# STM32.net
KiCad netlist of a schematic drawn in Altium Designer
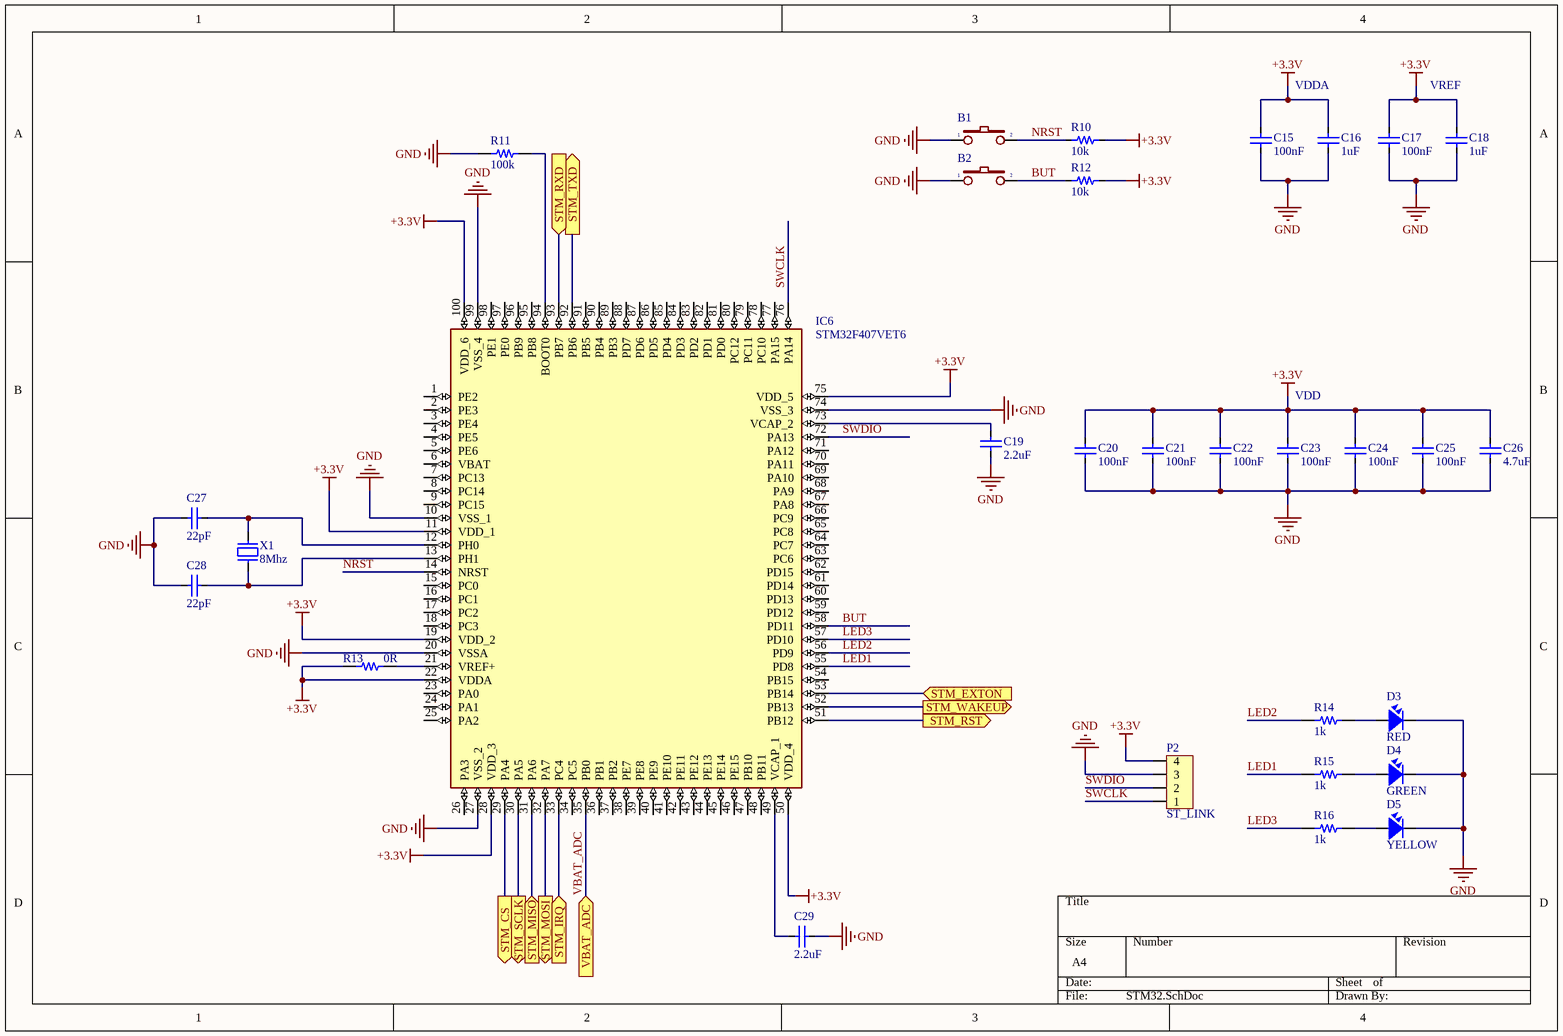
[diagram p0: STM32.SchDoc]

(export (version "E")
  (design (tool "Eeschema 10.0.6"))
  (components
    (comp (ref "B1")
      (value "Button 3x4x2.5")
      (footprint "Button 3x4x2.5")
      (libsource (lib "Dung Library") (part "Button 3x4x2.5"))
    )
    (comp (ref "B2")
      (value "Button 3x4x2.5")
      (footprint "BUTTON NGHIENG")
      (libsource (lib "Dung Library") (part "Button 3x4x2.5"))
    )
    (comp (ref "C15")
      (value "100nF")
      (footprint "CAP_0603")
      (description "Capacitor")
      (fields (field (name "PUBLISHER") "Altium Limited"))
      (libsource (lib "My Library") (part "CapSMD"))
    )
    (comp (ref "C16")
      (value "1uF")
      (footprint "CAP_0603")
      (description "Capacitor")
      (fields (field (name "PUBLISHER") "Altium Limited"))
      (libsource (lib "My Library") (part "CapSMD"))
    )
    (comp (ref "C17")
      (value "100nF")
      (footprint "CAP_0603")
      (description "Capacitor")
      (fields (field (name "PUBLISHER") "Altium Limited"))
      (libsource (lib "My Library") (part "CapSMD"))
    )
    (comp (ref "C18")
      (value "1uF")
      (footprint "CAP_0603")
      (description "Capacitor")
      (fields (field (name "PUBLISHER") "Altium Limited"))
      (libsource (lib "My Library") (part "CapSMD"))
    )
    (comp (ref "C19")
      (value "2.2uF")
      (footprint "CAP_0603")
      (description "Capacitor")
      (fields (field (name "PUBLISHER") "Altium Limited"))
      (libsource (lib "My Library") (part "CapSMD"))
    )
    (comp (ref "C20")
      (value "100nF")
      (footprint "CAP_0603")
      (description "Capacitor")
      (fields (field (name "PUBLISHER") "Altium Limited"))
      (libsource (lib "My Library") (part "CapSMD"))
    )
    (comp (ref "C21")
      (value "100nF")
      (footprint "CAP_0603")
      (description "Capacitor")
      (fields (field (name "PUBLISHER") "Altium Limited"))
      (libsource (lib "My Library") (part "CapSMD"))
    )
    (comp (ref "C22")
      (value "100nF")
      (footprint "CAP_0603")
      (description "Capacitor")
      (fields (field (name "PUBLISHER") "Altium Limited"))
      (libsource (lib "My Library") (part "CapSMD"))
    )
    (comp (ref "C23")
      (value "100nF")
      (footprint "CAP_0603")
      (description "Capacitor")
      (fields (field (name "PUBLISHER") "Altium Limited"))
      (libsource (lib "My Library") (part "CapSMD"))
    )
    (comp (ref "C24")
      (value "100nF")
      (footprint "CAP_0603")
      (description "Capacitor")
      (fields (field (name "PUBLISHER") "Altium Limited"))
      (libsource (lib "My Library") (part "CapSMD"))
    )
    (comp (ref "C25")
      (value "100nF")
      (footprint "CAP_0603")
      (description "Capacitor")
      (fields (field (name "PUBLISHER") "Altium Limited"))
      (libsource (lib "My Library") (part "CapSMD"))
    )
    (comp (ref "C26")
      (value "4.7uF")
      (footprint "CAP_0603")
      (description "Capacitor")
      (fields (field (name "PUBLISHER") "Altium Limited"))
      (libsource (lib "My Library") (part "CapSMD"))
    )
    (comp (ref "C27")
      (value "22pF")
      (footprint "CAP_0603")
      (description "Capacitor")
      (fields (field (name "PUBLISHER") "Altium Limited"))
      (libsource (lib "My Library") (part "CapSMD"))
    )
    (comp (ref "C28")
      (value "22pF")
      (footprint "CAP_0603")
      (description "Capacitor")
      (fields (field (name "PUBLISHER") "Altium Limited"))
      (libsource (lib "My Library") (part "CapSMD"))
    )
    (comp (ref "C29")
      (value "2.2uF")
      (footprint "CAP_0603")
      (description "Capacitor")
      (fields (field (name "PUBLISHER") "Altium Limited"))
      (libsource (lib "My Library") (part "CapSMD"))
    )
    (comp (ref "D3")
      (value "RED")
      (footprint "LED-0603-Red")
      (description "LED Single colour Green and Red")
      (libsource (lib "My Library") (part "LED"))
    )
    (comp (ref "D4")
      (value "GREEN")
      (footprint "LED-0603-Green")
      (description "LED Single colour Green and Red")
      (libsource (lib "My Library") (part "LED"))
    )
    (comp (ref "D5")
      (value "YELLOW")
      (footprint "LED-0603-Red")
      (description "LED Single colour Green and Red")
      (libsource (lib "My Library") (part "LED"))
    )
    (comp (ref "IC6")
      (value "STM32F407VET6")
      (footprint "STM32F407VET6")
      (libsource (lib "Dung Library") (part "STM32F407VET6"))
    )
    (comp (ref "P2")
      (value "ST_LINK")
      (footprint "HEADER4P-1.25")
      (description "Header IDC, 4 x 1 Pin Vertical 2.54mm Pitch (Non-Boxed, Male)")
      (fields
        (field (name "MANUFACTURER") "Würth Elektronik eiSos GmbH")
        (field (name "PARTNO") "613002143121")
        (field (name "CREATED BY") "Karrer Zheng")
      )
      (libsource (lib "My Library") (part "Header4"))
    )
    (comp (ref "R10")
      (value "10k")
      (footprint "RES-SMD-0603")
      (description "Resistor")
      (fields
        (field (name "MANUFACTURER") "Generic Components")
        (field (name "PUBLISHER") "Altium Hobart Technology Centre")
      )
      (libsource (lib "") (part "Resistor - SMD_1"))
    )
    (comp (ref "R11")
      (value "100k")
      (footprint "RES-SMD-0603")
      (description "Resistor")
      (fields
        (field (name "MANUFACTURER") "Generic Components")
        (field (name "PUBLISHER") "Altium Hobart Technology Centre")
      )
      (libsource (lib "My Library") (part "Resistor - SMD"))
    )
    (comp (ref "R12")
      (value "10k")
      (footprint "RES-SMD-0603")
      (description "Resistor")
      (fields
        (field (name "MANUFACTURER") "Generic Components")
        (field (name "PUBLISHER") "Altium Hobart Technology Centre")
      )
      (libsource (lib "") (part "Resistor - SMD_1"))
    )
    (comp (ref "R13")
      (value "0R")
      (footprint "RES-SMD-0603")
      (description "Resistor")
      (fields
        (field (name "MANUFACTURER") "Generic Components")
        (field (name "PUBLISHER") "Altium Hobart Technology Centre")
      )
      (libsource (lib "My Library") (part "Resistor - SMD"))
    )
    (comp (ref "R14")
      (value "1k")
      (footprint "RES-SMD-0603")
      (description "Resistor")
      (fields
        (field (name "MANUFACTURER") "Generic Components")
        (field (name "PUBLISHER") "Altium Hobart Technology Centre")
      )
      (libsource (lib "My Library") (part "Resistor - SMD"))
    )
    (comp (ref "R15")
      (value "1k")
      (footprint "RES-SMD-0603")
      (description "Resistor")
      (fields
        (field (name "MANUFACTURER") "Generic Components")
        (field (name "PUBLISHER") "Altium Hobart Technology Centre")
      )
      (libsource (lib "My Library") (part "Resistor - SMD"))
    )
    (comp (ref "R16")
      (value "1k")
      (footprint "RES-SMD-0603")
      (description "Resistor")
      (fields
        (field (name "MANUFACTURER") "Generic Components")
        (field (name "PUBLISHER") "Altium Hobart Technology Centre")
      )
      (libsource (lib "My Library") (part "Resistor - SMD"))
    )
    (comp (ref "X1")
      (value "8Mhz")
      (footprint "XTAL 5032 SMD")
      (description "Crystal For all Crystal 2pin.")
      (libsource (lib "My Library") (part "XT2"))
    )
  )
  (nets
    (net (code "1") (name "+3.3V") (class "Default")
      (node (ref "C15") (pin "2") (pinfunction "2_2") (pintype "passive"))
      (node (ref "C16") (pin "2") (pinfunction "2_2") (pintype "passive"))
      (node (ref "C17") (pin "2") (pinfunction "2_2") (pintype "passive"))
      (node (ref "C18") (pin "2") (pinfunction "2_2") (pintype "passive"))
      (node (ref "C20") (pin "2") (pinfunction "2_2") (pintype "passive"))
      (node (ref "C21") (pin "2") (pinfunction "2_2") (pintype "passive"))
      (node (ref "C22") (pin "2") (pinfunction "2_2") (pintype "passive"))
      (node (ref "C23") (pin "2") (pinfunction "2_2") (pintype "passive"))
      (node (ref "C24") (pin "2") (pinfunction "2_2") (pintype "passive"))
      (node (ref "C25") (pin "2") (pinfunction "2_2") (pintype "passive"))
      (node (ref "C26") (pin "2") (pinfunction "2_2") (pintype "passive"))
      (node (ref "IC6") (pin "100") (pinfunction "VDD_6_100") (pintype "bidirectional"))
      (node (ref "IC6") (pin "11") (pinfunction "VDD_1_11") (pintype "bidirectional"))
      (node (ref "IC6") (pin "19") (pinfunction "VDD_2_19") (pintype "bidirectional"))
      (node (ref "IC6") (pin "22") (pinfunction "VDDA_22") (pintype "bidirectional"))
      (node (ref "IC6") (pin "28") (pinfunction "VDD_3_28") (pintype "bidirectional"))
      (node (ref "IC6") (pin "50") (pinfunction "VDD_4_50") (pintype "bidirectional"))
      (node (ref "IC6") (pin "75") (pinfunction "VDD_5_75") (pintype "bidirectional"))
      (node (ref "P2") (pin "4") (pinfunction "4_4") (pintype "passive"))
      (node (ref "R10") (pin "1") (pinfunction "1_1") (pintype "passive"))
      (node (ref "R12") (pin "1") (pinfunction "1_1") (pintype "passive"))
      (node (ref "R13") (pin "2") (pinfunction "2_2") (pintype "passive"))
    )
    (net (code "2") (name "/BUT") (class "Default")
      (node (ref "B2") (pin "2") (pinfunction "2_2") (pintype "passive"))
      (node (ref "IC6") (pin "58") (pinfunction "PD11_58") (pintype "bidirectional"))
      (node (ref "R12") (pin "2") (pinfunction "2_2") (pintype "passive"))
    )
    (net (code "3") (name "/LED1") (class "Default")
      (node (ref "IC6") (pin "55") (pinfunction "PD8_55") (pintype "bidirectional"))
      (node (ref "R15") (pin "2") (pinfunction "2_2") (pintype "passive"))
    )
    (net (code "4") (name "/LED2") (class "Default")
      (node (ref "IC6") (pin "56") (pinfunction "PD9_56") (pintype "bidirectional"))
      (node (ref "R14") (pin "2") (pinfunction "2_2") (pintype "passive"))
    )
    (net (code "5") (name "/LED3") (class "Default")
      (node (ref "IC6") (pin "57") (pinfunction "PD10_57") (pintype "bidirectional"))
      (node (ref "R16") (pin "2") (pinfunction "2_2") (pintype "passive"))
    )
    (net (code "6") (name "/NRST") (class "Default")
      (node (ref "B1") (pin "2") (pinfunction "2_2") (pintype "passive"))
      (node (ref "IC6") (pin "14") (pinfunction "NRST_14") (pintype "bidirectional"))
      (node (ref "R10") (pin "2") (pinfunction "2_2") (pintype "passive"))
    )
    (net (code "7") (name "/STM_CS") (class "Default")
      (node (ref "IC6") (pin "29") (pinfunction "PA4_29") (pintype "bidirectional"))
    )
    (net (code "8") (name "/STM_EXTON") (class "Default")
      (node (ref "IC6") (pin "53") (pinfunction "PB14_53") (pintype "bidirectional"))
    )
    (net (code "9") (name "/STM_IRQ") (class "Default")
      (node (ref "IC6") (pin "33") (pinfunction "PC4_33") (pintype "bidirectional"))
    )
    (net (code "10") (name "/STM_MISO") (class "Default")
      (node (ref "IC6") (pin "31") (pinfunction "PA6_31") (pintype "bidirectional"))
    )
    (net (code "11") (name "/STM_MOSI") (class "Default")
      (node (ref "IC6") (pin "32") (pinfunction "PA7_32") (pintype "bidirectional"))
    )
    (net (code "12") (name "/STM_RST") (class "Default")
      (node (ref "IC6") (pin "51") (pinfunction "PB12_51") (pintype "bidirectional"))
    )
    (net (code "13") (name "/STM_RXD") (class "Default")
      (node (ref "IC6") (pin "93") (pinfunction "PB7_93") (pintype "bidirectional"))
    )
    (net (code "14") (name "/STM_SCLK") (class "Default")
      (node (ref "IC6") (pin "30") (pinfunction "PA5_30") (pintype "bidirectional"))
    )
    (net (code "15") (name "/STM_TXD") (class "Default")
      (node (ref "IC6") (pin "92") (pinfunction "PB6_92") (pintype "bidirectional"))
    )
    (net (code "16") (name "/STM_WAKEUP") (class "Default")
      (node (ref "IC6") (pin "52") (pinfunction "PB13_52") (pintype "bidirectional"))
    )
    (net (code "17") (name "/SWCLK") (class "Default")
      (node (ref "IC6") (pin "76") (pinfunction "PA14_76") (pintype "bidirectional"))
      (node (ref "P2") (pin "1") (pinfunction "1_1") (pintype "passive"))
    )
    (net (code "18") (name "/SWDIO") (class "Default")
      (node (ref "IC6") (pin "72") (pinfunction "PA13_72") (pintype "bidirectional"))
      (node (ref "P2") (pin "2") (pinfunction "2_2") (pintype "passive"))
    )
    (net (code "19") (name "/VBAT_ADC") (class "Default")
      (node (ref "IC6") (pin "35") (pinfunction "PB0_35") (pintype "bidirectional"))
    )
    (net (code "20") (name "GND") (class "Default")
      (node (ref "B1") (pin "1") (pinfunction "1_1") (pintype "passive"))
      (node (ref "B2") (pin "1") (pinfunction "1_1") (pintype "passive"))
      (node (ref "C15") (pin "1") (pinfunction "1_1") (pintype "passive"))
      (node (ref "C16") (pin "1") (pinfunction "1_1") (pintype "passive"))
      (node (ref "C17") (pin "1") (pinfunction "1_1") (pintype "passive"))
      (node (ref "C18") (pin "1") (pinfunction "1_1") (pintype "passive"))
      (node (ref "C19") (pin "2") (pinfunction "2_2") (pintype "passive"))
      (node (ref "C20") (pin "1") (pinfunction "1_1") (pintype "passive"))
      (node (ref "C21") (pin "1") (pinfunction "1_1") (pintype "passive"))
      (node (ref "C22") (pin "1") (pinfunction "1_1") (pintype "passive"))
      (node (ref "C23") (pin "1") (pinfunction "1_1") (pintype "passive"))
      (node (ref "C24") (pin "1") (pinfunction "1_1") (pintype "passive"))
      (node (ref "C25") (pin "1") (pinfunction "1_1") (pintype "passive"))
      (node (ref "C26") (pin "1") (pinfunction "1_1") (pintype "passive"))
      (node (ref "C27") (pin "1") (pinfunction "1_1") (pintype "passive"))
      (node (ref "C28") (pin "1") (pinfunction "1_1") (pintype "passive"))
      (node (ref "C29") (pin "2") (pinfunction "2_2") (pintype "passive"))
      (node (ref "D3") (pin "2") (pinfunction "2_2") (pintype "passive"))
      (node (ref "D4") (pin "2") (pinfunction "2_2") (pintype "passive"))
      (node (ref "D5") (pin "2") (pinfunction "2_2") (pintype "passive"))
      (node (ref "IC6") (pin "10") (pinfunction "VSS_1_10") (pintype "bidirectional"))
      (node (ref "IC6") (pin "20") (pinfunction "VSSA_20") (pintype "bidirectional"))
      (node (ref "IC6") (pin "27") (pinfunction "VSS_2_27") (pintype "bidirectional"))
      (node (ref "IC6") (pin "74") (pinfunction "VSS_3_74") (pintype "bidirectional"))
      (node (ref "IC6") (pin "99") (pinfunction "VSS_4_99") (pintype "bidirectional"))
      (node (ref "P2") (pin "3") (pinfunction "3_3") (pintype "passive"))
      (node (ref "R11") (pin "1") (pinfunction "1_1") (pintype "passive"))
    )
    (net (code "21") (name "Net-(D3-Pad1)") (class "Default")
      (node (ref "D3") (pin "1") (pinfunction "1_1") (pintype "passive"))
      (node (ref "R14") (pin "1") (pinfunction "1_1") (pintype "passive"))
    )
    (net (code "22") (name "Net-(D4-Pad1)") (class "Default")
      (node (ref "D4") (pin "1") (pinfunction "1_1") (pintype "passive"))
      (node (ref "R15") (pin "1") (pinfunction "1_1") (pintype "passive"))
    )
    (net (code "23") (name "Net-(D5-Pad1)") (class "Default")
      (node (ref "D5") (pin "1") (pinfunction "1_1") (pintype "passive"))
      (node (ref "R16") (pin "1") (pinfunction "1_1") (pintype "passive"))
    )
    (net (code "24") (name "Net-(IC6-BOOT0)") (class "Default")
      (node (ref "IC6") (pin "94") (pinfunction "BOOT0_94") (pintype "bidirectional"))
      (node (ref "R11") (pin "2") (pinfunction "2_2") (pintype "passive"))
    )
    (net (code "25") (name "Net-(IC6-PH0)") (class "Default")
      (node (ref "C27") (pin "2") (pinfunction "2_2") (pintype "passive"))
      (node (ref "IC6") (pin "12") (pinfunction "PH0_12") (pintype "bidirectional"))
      (node (ref "X1") (pin "1") (pinfunction "1_1") (pintype "passive"))
    )
    (net (code "26") (name "Net-(IC6-PH1)") (class "Default")
      (node (ref "C28") (pin "2") (pinfunction "2_2") (pintype "passive"))
      (node (ref "IC6") (pin "13") (pinfunction "PH1_13") (pintype "bidirectional"))
      (node (ref "X1") (pin "2") (pinfunction "2_2") (pintype "passive"))
    )
    (net (code "27") (name "Net-(IC6-VCAP_1)") (class "Default")
      (node (ref "C29") (pin "1") (pinfunction "1_1") (pintype "passive"))
      (node (ref "IC6") (pin "49") (pinfunction "VCAP_1_49") (pintype "bidirectional"))
    )
    (net (code "28") (name "Net-(IC6-VCAP_2)") (class "Default")
      (node (ref "C19") (pin "1") (pinfunction "1_1") (pintype "passive"))
      (node (ref "IC6") (pin "73") (pinfunction "VCAP_2_73") (pintype "bidirectional"))
    )
    (net (code "29") (name "Net-(IC6-VREF+)") (class "Default")
      (node (ref "IC6") (pin "21") (pinfunction "VREF+_21") (pintype "bidirectional"))
      (node (ref "R13") (pin "1") (pinfunction "1_1") (pintype "passive"))
    )
    (net (code "30") (name "unconnected-(IC6-PA0-Pad23)") (class "Default")
      (node (ref "IC6") (pin "23") (pinfunction "PA0_23") (pintype "bidirectional"))
    )
    (net (code "31") (name "unconnected-(IC6-PA1-Pad24)") (class "Default")
      (node (ref "IC6") (pin "24") (pinfunction "PA1_24") (pintype "bidirectional"))
    )
    (net (code "32") (name "unconnected-(IC6-PA2-Pad25)") (class "Default")
      (node (ref "IC6") (pin "25") (pinfunction "PA2_25") (pintype "bidirectional"))
    )
    (net (code "33") (name "unconnected-(IC6-PA3-Pad26)") (class "Default")
      (node (ref "IC6") (pin "26") (pinfunction "PA3_26") (pintype "bidirectional"))
    )
    (net (code "34") (name "unconnected-(IC6-PA8-Pad67)") (class "Default")
      (node (ref "IC6") (pin "67") (pinfunction "PA8_67") (pintype "bidirectional"))
    )
    (net (code "35") (name "unconnected-(IC6-PA9-Pad68)") (class "Default")
      (node (ref "IC6") (pin "68") (pinfunction "PA9_68") (pintype "bidirectional"))
    )
    (net (code "36") (name "unconnected-(IC6-PA10-Pad69)") (class "Default")
      (node (ref "IC6") (pin "69") (pinfunction "PA10_69") (pintype "bidirectional"))
    )
    (net (code "37") (name "unconnected-(IC6-PA11-Pad70)") (class "Default")
      (node (ref "IC6") (pin "70") (pinfunction "PA11_70") (pintype "bidirectional"))
    )
    (net (code "38") (name "unconnected-(IC6-PA12-Pad71)") (class "Default")
      (node (ref "IC6") (pin "71") (pinfunction "PA12_71") (pintype "bidirectional"))
    )
    (net (code "39") (name "unconnected-(IC6-PA15-Pad77)") (class "Default")
      (node (ref "IC6") (pin "77") (pinfunction "PA15_77") (pintype "bidirectional"))
    )
    (net (code "40") (name "unconnected-(IC6-PB1-Pad36)") (class "Default")
      (node (ref "IC6") (pin "36") (pinfunction "PB1_36") (pintype "bidirectional"))
    )
    (net (code "41") (name "unconnected-(IC6-PB2-Pad37)") (class "Default")
      (node (ref "IC6") (pin "37") (pinfunction "PB2_37") (pintype "bidirectional"))
    )
    (net (code "42") (name "unconnected-(IC6-PB3-Pad89)") (class "Default")
      (node (ref "IC6") (pin "89") (pinfunction "PB3_89") (pintype "bidirectional"))
    )
    (net (code "43") (name "unconnected-(IC6-PB4-Pad90)") (class "Default")
      (node (ref "IC6") (pin "90") (pinfunction "PB4_90") (pintype "bidirectional"))
    )
    (net (code "44") (name "unconnected-(IC6-PB5-Pad91)") (class "Default")
      (node (ref "IC6") (pin "91") (pinfunction "PB5_91") (pintype "bidirectional"))
    )
    (net (code "45") (name "unconnected-(IC6-PB8-Pad95)") (class "Default")
      (node (ref "IC6") (pin "95") (pinfunction "PB8_95") (pintype "bidirectional"))
    )
    (net (code "46") (name "unconnected-(IC6-PB9-Pad96)") (class "Default")
      (node (ref "IC6") (pin "96") (pinfunction "PB9_96") (pintype "bidirectional"))
    )
    (net (code "47") (name "unconnected-(IC6-PB10-Pad47)") (class "Default")
      (node (ref "IC6") (pin "47") (pinfunction "PB10_47") (pintype "bidirectional"))
    )
    (net (code "48") (name "unconnected-(IC6-PB11-Pad48)") (class "Default")
      (node (ref "IC6") (pin "48") (pinfunction "PB11_48") (pintype "bidirectional"))
    )
    (net (code "49") (name "unconnected-(IC6-PB15-Pad54)") (class "Default")
      (node (ref "IC6") (pin "54") (pinfunction "PB15_54") (pintype "bidirectional"))
    )
    (net (code "50") (name "unconnected-(IC6-PC0-Pad15)") (class "Default")
      (node (ref "IC6") (pin "15") (pinfunction "PC0_15") (pintype "bidirectional"))
    )
    (net (code "51") (name "unconnected-(IC6-PC1-Pad16)") (class "Default")
      (node (ref "IC6") (pin "16") (pinfunction "PC1_16") (pintype "bidirectional"))
    )
    (net (code "52") (name "unconnected-(IC6-PC2-Pad17)") (class "Default")
      (node (ref "IC6") (pin "17") (pinfunction "PC2_17") (pintype "bidirectional"))
    )
    (net (code "53") (name "unconnected-(IC6-PC3-Pad18)") (class "Default")
      (node (ref "IC6") (pin "18") (pinfunction "PC3_18") (pintype "bidirectional"))
    )
    (net (code "54") (name "unconnected-(IC6-PC5-Pad34)") (class "Default")
      (node (ref "IC6") (pin "34") (pinfunction "PC5_34") (pintype "bidirectional"))
    )
    (net (code "55") (name "unconnected-(IC6-PC6-Pad63)") (class "Default")
      (node (ref "IC6") (pin "63") (pinfunction "PC6_63") (pintype "bidirectional"))
    )
    (net (code "56") (name "unconnected-(IC6-PC7-Pad64)") (class "Default")
      (node (ref "IC6") (pin "64") (pinfunction "PC7_64") (pintype "bidirectional"))
    )
    (net (code "57") (name "unconnected-(IC6-PC8-Pad65)") (class "Default")
      (node (ref "IC6") (pin "65") (pinfunction "PC8_65") (pintype "bidirectional"))
    )
    (net (code "58") (name "unconnected-(IC6-PC9-Pad66)") (class "Default")
      (node (ref "IC6") (pin "66") (pinfunction "PC9_66") (pintype "bidirectional"))
    )
    (net (code "59") (name "unconnected-(IC6-PC10-Pad78)") (class "Default")
      (node (ref "IC6") (pin "78") (pinfunction "PC10_78") (pintype "bidirectional"))
    )
    (net (code "60") (name "unconnected-(IC6-PC11-Pad79)") (class "Default")
      (node (ref "IC6") (pin "79") (pinfunction "PC11_79") (pintype "bidirectional"))
    )
    (net (code "61") (name "unconnected-(IC6-PC12-Pad80)") (class "Default")
      (node (ref "IC6") (pin "80") (pinfunction "PC12_80") (pintype "bidirectional"))
    )
    (net (code "62") (name "unconnected-(IC6-PC13-Pad7)") (class "Default")
      (node (ref "IC6") (pin "7") (pinfunction "PC13_7") (pintype "bidirectional"))
    )
    (net (code "63") (name "unconnected-(IC6-PC14-Pad8)") (class "Default")
      (node (ref "IC6") (pin "8") (pinfunction "PC14_8") (pintype "bidirectional"))
    )
    (net (code "64") (name "unconnected-(IC6-PC15-Pad9)") (class "Default")
      (node (ref "IC6") (pin "9") (pinfunction "PC15_9") (pintype "bidirectional"))
    )
    (net (code "65") (name "unconnected-(IC6-PD0-Pad81)") (class "Default")
      (node (ref "IC6") (pin "81") (pinfunction "PD0_81") (pintype "bidirectional"))
    )
    (net (code "66") (name "unconnected-(IC6-PD1-Pad82)") (class "Default")
      (node (ref "IC6") (pin "82") (pinfunction "PD1_82") (pintype "bidirectional"))
    )
    (net (code "67") (name "unconnected-(IC6-PD2-Pad83)") (class "Default")
      (node (ref "IC6") (pin "83") (pinfunction "PD2_83") (pintype "bidirectional"))
    )
    (net (code "68") (name "unconnected-(IC6-PD3-Pad84)") (class "Default")
      (node (ref "IC6") (pin "84") (pinfunction "PD3_84") (pintype "bidirectional"))
    )
    (net (code "69") (name "unconnected-(IC6-PD4-Pad85)") (class "Default")
      (node (ref "IC6") (pin "85") (pinfunction "PD4_85") (pintype "bidirectional"))
    )
    (net (code "70") (name "unconnected-(IC6-PD5-Pad86)") (class "Default")
      (node (ref "IC6") (pin "86") (pinfunction "PD5_86") (pintype "bidirectional"))
    )
    (net (code "71") (name "unconnected-(IC6-PD6-Pad87)") (class "Default")
      (node (ref "IC6") (pin "87") (pinfunction "PD6_87") (pintype "bidirectional"))
    )
    (net (code "72") (name "unconnected-(IC6-PD7-Pad88)") (class "Default")
      (node (ref "IC6") (pin "88") (pinfunction "PD7_88") (pintype "bidirectional"))
    )
    (net (code "73") (name "unconnected-(IC6-PD12-Pad59)") (class "Default")
      (node (ref "IC6") (pin "59") (pinfunction "PD12_59") (pintype "bidirectional"))
    )
    (net (code "74") (name "unconnected-(IC6-PD13-Pad60)") (class "Default")
      (node (ref "IC6") (pin "60") (pinfunction "PD13_60") (pintype "bidirectional"))
    )
    (net (code "75") (name "unconnected-(IC6-PD14-Pad61)") (class "Default")
      (node (ref "IC6") (pin "61") (pinfunction "PD14_61") (pintype "bidirectional"))
    )
    (net (code "76") (name "unconnected-(IC6-PD15-Pad62)") (class "Default")
      (node (ref "IC6") (pin "62") (pinfunction "PD15_62") (pintype "bidirectional"))
    )
    (net (code "77") (name "unconnected-(IC6-PE0-Pad97)") (class "Default")
      (node (ref "IC6") (pin "97") (pinfunction "PE0_97") (pintype "bidirectional"))
    )
    (net (code "78") (name "unconnected-(IC6-PE1-Pad98)") (class "Default")
      (node (ref "IC6") (pin "98") (pinfunction "PE1_98") (pintype "bidirectional"))
    )
    (net (code "79") (name "unconnected-(IC6-PE2-Pad1)") (class "Default")
      (node (ref "IC6") (pin "1") (pinfunction "PE2_1") (pintype "bidirectional"))
    )
    (net (code "80") (name "unconnected-(IC6-PE3-Pad2)") (class "Default")
      (node (ref "IC6") (pin "2") (pinfunction "PE3_2") (pintype "bidirectional"))
    )
    (net (code "81") (name "unconnected-(IC6-PE4-Pad3)") (class "Default")
      (node (ref "IC6") (pin "3") (pinfunction "PE4_3") (pintype "bidirectional"))
    )
    (net (code "82") (name "unconnected-(IC6-PE5-Pad4)") (class "Default")
      (node (ref "IC6") (pin "4") (pinfunction "PE5_4") (pintype "bidirectional"))
    )
    (net (code "83") (name "unconnected-(IC6-PE6-Pad5)") (class "Default")
      (node (ref "IC6") (pin "5") (pinfunction "PE6_5") (pintype "bidirectional"))
    )
    (net (code "84") (name "unconnected-(IC6-PE7-Pad38)") (class "Default")
      (node (ref "IC6") (pin "38") (pinfunction "PE7_38") (pintype "bidirectional"))
    )
    (net (code "85") (name "unconnected-(IC6-PE8-Pad39)") (class "Default")
      (node (ref "IC6") (pin "39") (pinfunction "PE8_39") (pintype "bidirectional"))
    )
    (net (code "86") (name "unconnected-(IC6-PE9-Pad40)") (class "Default")
      (node (ref "IC6") (pin "40") (pinfunction "PE9_40") (pintype "bidirectional"))
    )
    (net (code "87") (name "unconnected-(IC6-PE10-Pad41)") (class "Default")
      (node (ref "IC6") (pin "41") (pinfunction "PE10_41") (pintype "bidirectional"))
    )
    (net (code "88") (name "unconnected-(IC6-PE11-Pad42)") (class "Default")
      (node (ref "IC6") (pin "42") (pinfunction "PE11_42") (pintype "bidirectional"))
    )
    (net (code "89") (name "unconnected-(IC6-PE12-Pad43)") (class "Default")
      (node (ref "IC6") (pin "43") (pinfunction "PE12_43") (pintype "bidirectional"))
    )
    (net (code "90") (name "unconnected-(IC6-PE13-Pad44)") (class "Default")
      (node (ref "IC6") (pin "44") (pinfunction "PE13_44") (pintype "bidirectional"))
    )
    (net (code "91") (name "unconnected-(IC6-PE14-Pad45)") (class "Default")
      (node (ref "IC6") (pin "45") (pinfunction "PE14_45") (pintype "bidirectional"))
    )
    (net (code "92") (name "unconnected-(IC6-PE15-Pad46)") (class "Default")
      (node (ref "IC6") (pin "46") (pinfunction "PE15_46") (pintype "bidirectional"))
    )
    (net (code "93") (name "unconnected-(IC6-VBAT-Pad6)") (class "Default")
      (node (ref "IC6") (pin "6") (pinfunction "VBAT_6") (pintype "bidirectional"))
    )
  )
)
